# NukeNanny.net
KiCad netlist of a schematic drawn in EAGLE
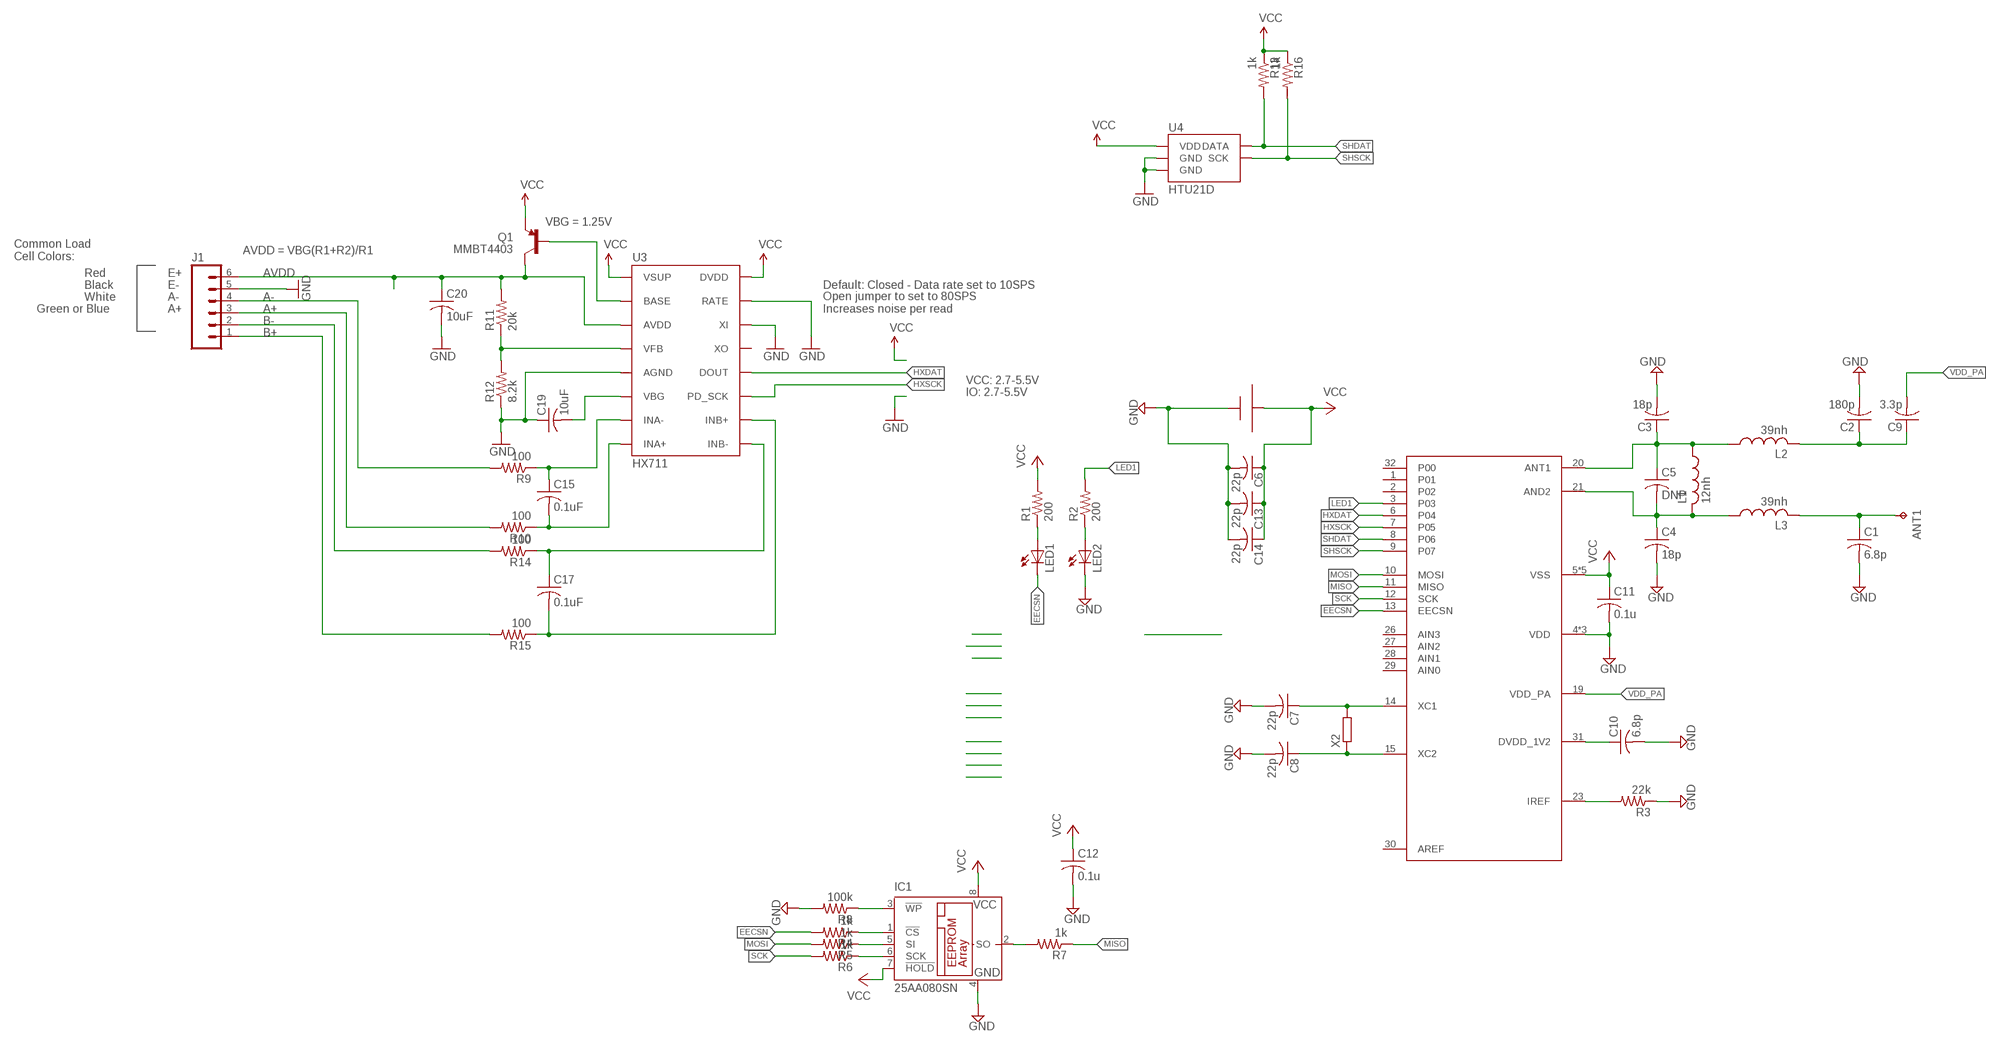
[diagram p0: schematic, sheet 1]

(export (version "E")
  (design (tool "Eeschema 10.0.6"))
  (components
    (comp (ref "ANT1")
      (value "TPB2,54")
      (footprint "eagle-import:B2,54")
      (libsource (lib "eagle-import") (part "TPB2,54"))
    )
    (comp (ref "C1")
      (value "6.8p")
      (footprint "eagle-import:C0805")
      (libsource (lib "eagle-import") (part "C-USC0805"))
    )
    (comp (ref "C2")
      (value "180p")
      (footprint "eagle-import:C0805")
      (libsource (lib "eagle-import") (part "C-USC0805"))
    )
    (comp (ref "C3")
      (value "18p")
      (footprint "eagle-import:C0805")
      (libsource (lib "eagle-import") (part "C-USC0805"))
    )
    (comp (ref "C4")
      (value "18p")
      (footprint "eagle-import:C0805")
      (libsource (lib "eagle-import") (part "C-USC0805"))
    )
    (comp (ref "C5")
      (value "DNP")
      (footprint "eagle-import:C0805")
      (libsource (lib "eagle-import") (part "C-USC0805"))
    )
    (comp (ref "C6")
      (value "22p")
      (footprint "eagle-import:C1206")
      (libsource (lib "eagle-import") (part "C-USC1206"))
    )
    (comp (ref "C7")
      (value "22p")
      (footprint "eagle-import:C0805")
      (libsource (lib "eagle-import") (part "C-USC0805"))
    )
    (comp (ref "C8")
      (value "22p")
      (footprint "eagle-import:C0805")
      (libsource (lib "eagle-import") (part "C-USC0805"))
    )
    (comp (ref "C9")
      (value "3.3p")
      (footprint "eagle-import:C0805")
      (libsource (lib "eagle-import") (part "C-USC0805"))
    )
    (comp (ref "C10")
      (value "6.8p")
      (footprint "eagle-import:C0805")
      (libsource (lib "eagle-import") (part "C-USC0805"))
    )
    (comp (ref "C11")
      (value "0.1u")
      (footprint "eagle-import:C0805")
      (libsource (lib "eagle-import") (part "C-USC0805"))
    )
    (comp (ref "C12")
      (value "0.1u")
      (footprint "eagle-import:C0805")
      (libsource (lib "eagle-import") (part "C-USC0805"))
    )
    (comp (ref "C13")
      (value "22p")
      (footprint "eagle-import:C1206")
      (libsource (lib "eagle-import") (part "C-USC1206"))
    )
    (comp (ref "C14")
      (value "22p")
      (footprint "eagle-import:C1206")
      (libsource (lib "eagle-import") (part "C-USC1206"))
    )
    (comp (ref "C15")
      (value "0.1uF")
      (footprint "eagle-import:C0805")
      (libsource (lib "eagle-import") (part "C-USC0805"))
    )
    (comp (ref "C17")
      (value "0.1uF")
      (footprint "eagle-import:C0805")
      (libsource (lib "eagle-import") (part "C-USC0805"))
    )
    (comp (ref "C19")
      (value "10uF")
      (footprint "eagle-import:C0805")
      (libsource (lib "eagle-import") (part "C-USC0805"))
    )
    (comp (ref "C20")
      (value "10uF")
      (footprint "eagle-import:C0805")
      (libsource (lib "eagle-import") (part "C-USC0805"))
    )
    (comp (ref "IC1")
      (value "25AA080SN")
      (footprint "eagle-import:SO-08")
      (fields (field (name "MF") "MICROCHIP") (field (name "MPN") "25AA080/SN"))
      (libsource (lib "eagle-import") (part "25SNAA080"))
    )
    (comp (ref "J1")
      (value "M06SMD-1MM")
      (footprint "eagle-import:1X06-1MM")
      (libsource (lib "eagle-import") (part "M06SMD-1MM"))
    )
    (comp (ref "L1")
      (value "12nh")
      (footprint "eagle-import:L2012C")
      (libsource (lib "eagle-import") (part "L-USL2012C"))
    )
    (comp (ref "L2")
      (value "39nh")
      (footprint "eagle-import:L2012C")
      (libsource (lib "eagle-import") (part "L-USL2012C"))
    )
    (comp (ref "L3")
      (value "39nh")
      (footprint "eagle-import:L2012C")
      (libsource (lib "eagle-import") (part "L-USL2012C"))
    )
    (comp (ref "LED1")
      (value "LEDCHIP-LED0805")
      (footprint "eagle-import:CHIP-LED0805")
      (libsource (lib "eagle-import") (part "LEDCHIP-LED0805"))
    )
    (comp (ref "LED2")
      (value "LEDCHIP-LED0805")
      (footprint "eagle-import:CHIP-LED0805")
      (libsource (lib "eagle-import") (part "LEDCHIP-LED0805"))
    )
    (comp (ref "Q1")
      (value "MMBT4403")
      (footprint "eagle-import:SOT23-3")
      (libsource (lib "eagle-import") (part "TRANSISTOR_PNPMMBT4403"))
    )
    (comp (ref "R1")
      (value "200")
      (footprint "eagle-import:R0805")
      (libsource (lib "eagle-import") (part "R-US_R0805"))
    )
    (comp (ref "R2")
      (value "200")
      (footprint "eagle-import:R0805")
      (libsource (lib "eagle-import") (part "R-US_R0805"))
    )
    (comp (ref "R3")
      (value "22k")
      (footprint "eagle-import:R0805")
      (libsource (lib "eagle-import") (part "R-US_R0805"))
    )
    (comp (ref "R4")
      (value "1k")
      (footprint "eagle-import:R0805")
      (libsource (lib "eagle-import") (part "R-US_R0805"))
    )
    (comp (ref "R5")
      (value "1k")
      (footprint "eagle-import:R0805")
      (libsource (lib "eagle-import") (part "R-US_R0805"))
    )
    (comp (ref "R6")
      (value "1k")
      (footprint "eagle-import:R0805")
      (libsource (lib "eagle-import") (part "R-US_R0805"))
    )
    (comp (ref "R7")
      (value "1k")
      (footprint "eagle-import:R0805")
      (libsource (lib "eagle-import") (part "R-US_R0805"))
    )
    (comp (ref "R8")
      (value "100k")
      (footprint "eagle-import:R0805")
      (libsource (lib "eagle-import") (part "R-US_R0805"))
    )
    (comp (ref "R9")
      (value "100")
      (footprint "eagle-import:R0805")
      (libsource (lib "eagle-import") (part "R-US_R0805"))
    )
    (comp (ref "R10")
      (value "100")
      (footprint "eagle-import:R0805")
      (libsource (lib "eagle-import") (part "R-US_R0805"))
    )
    (comp (ref "R11")
      (value "20k")
      (footprint "eagle-import:R0805")
      (libsource (lib "eagle-import") (part "R-US_R0805"))
    )
    (comp (ref "R12")
      (value "8.2k")
      (footprint "eagle-import:R0805")
      (libsource (lib "eagle-import") (part "R-US_R0805"))
    )
    (comp (ref "R13")
      (value "1k")
      (footprint "eagle-import:R0805")
      (libsource (lib "eagle-import") (part "R-US_R0805"))
    )
    (comp (ref "R14")
      (value "100")
      (footprint "eagle-import:R0805")
      (libsource (lib "eagle-import") (part "R-US_R0805"))
    )
    (comp (ref "R15")
      (value "100")
      (footprint "eagle-import:R0805")
      (libsource (lib "eagle-import") (part "R-US_R0805"))
    )
    (comp (ref "R16")
      (value "1k")
      (footprint "eagle-import:R0805")
      (libsource (lib "eagle-import") (part "R-US_R0805"))
    )
    (comp (ref "U$1")
      (value "NRF9E5")
      (footprint "eagle-import:32QFN-THIN")
      (libsource (lib "eagle-import") (part "NRF9E5"))
    )
    (comp (ref "U1")
      (value "CR2032")
      (footprint "eagle-import:SMT_CR2032_HOLDER")
      (libsource (lib "eagle-import") (part "CR2032"))
    )
    (comp (ref "U3")
      (value "HX711")
      (footprint "eagle-import:SO16")
      (libsource (lib "eagle-import") (part "HX711HX711"))
    )
    (comp (ref "U4")
      (value "HTU21D")
      (footprint "eagle-import:HTU21D")
      (libsource (lib "eagle-import") (part "HTU21DSMD"))
    )
    (comp (ref "X2")
      (value "R-EU_R3225")
      (footprint "eagle-import:R3225")
      (libsource (lib "eagle-import") (part "R-EU_R3225"))
    )
  )
  (nets
    (net (code "1") (name "/A+") (class "Default")
      (node (ref "J1") (pin "3") (pinfunction "3_3") (pintype "passive"))
      (node (ref "R10") (pin "2") (pinfunction "2_2") (pintype "passive"))
    )
    (net (code "2") (name "/A-") (class "Default")
      (node (ref "J1") (pin "4") (pinfunction "4_4") (pintype "passive"))
      (node (ref "R9") (pin "2") (pinfunction "2_2") (pintype "passive"))
    )
    (net (code "3") (name "/AVDD") (class "Default")
      (node (ref "C20") (pin "1") (pinfunction "1_1") (pintype "passive"))
      (node (ref "J1") (pin "6") (pinfunction "6_6") (pintype "passive"))
      (node (ref "Q1") (pin "3") (pinfunction "C_3") (pintype "passive"))
      (node (ref "R11") (pin "2") (pinfunction "2_2") (pintype "passive"))
      (node (ref "U3") (pin "3") (pinfunction "AVDD_3") (pintype "bidirectional"))
    )
    (net (code "4") (name "/B+") (class "Default")
      (node (ref "J1") (pin "1") (pinfunction "1_1") (pintype "passive"))
      (node (ref "R15") (pin "2") (pinfunction "2_2") (pintype "passive"))
    )
    (net (code "5") (name "/B-") (class "Default")
      (node (ref "J1") (pin "2") (pinfunction "2_2") (pintype "passive"))
      (node (ref "R14") (pin "2") (pinfunction "2_2") (pintype "passive"))
    )
    (net (code "6") (name "EECSN") (class "Default")
      (node (ref "LED1") (pin "C") (pinfunction "C_C") (pintype "passive"))
      (node (ref "R4") (pin "2") (pinfunction "2_2") (pintype "passive"))
      (node (ref "U$1") (pin "13") (pinfunction "EECSN_13") (pintype "bidirectional"))
    )
    (net (code "7") (name "GND") (class "Default")
      (node (ref "C1") (pin "2") (pinfunction "2_2") (pintype "passive"))
      (node (ref "C10") (pin "2") (pinfunction "2_2") (pintype "passive"))
      (node (ref "C11") (pin "2") (pinfunction "2_2") (pintype "passive"))
      (node (ref "C12") (pin "2") (pinfunction "2_2") (pintype "passive"))
      (node (ref "C13") (pin "2") (pinfunction "2_2") (pintype "passive"))
      (node (ref "C14") (pin "2") (pinfunction "2_2") (pintype "passive"))
      (node (ref "C19") (pin "1") (pinfunction "1_1") (pintype "passive"))
      (node (ref "C2") (pin "2") (pinfunction "2_2") (pintype "passive"))
      (node (ref "C20") (pin "2") (pinfunction "2_2") (pintype "passive"))
      (node (ref "C3") (pin "2") (pinfunction "2_2") (pintype "passive"))
      (node (ref "C4") (pin "2") (pinfunction "2_2") (pintype "passive"))
      (node (ref "C6") (pin "2") (pinfunction "2_2") (pintype "passive"))
      (node (ref "C7") (pin "2") (pinfunction "2_2") (pintype "passive"))
      (node (ref "C8") (pin "2") (pinfunction "2_2") (pintype "passive"))
      (node (ref "IC1") (pin "4") (pinfunction "GND_4") (pintype "power_in"))
      (node (ref "J1") (pin "5") (pinfunction "5_5") (pintype "passive"))
      (node (ref "LED2") (pin "C") (pinfunction "C_C") (pintype "passive"))
      (node (ref "R12") (pin "1") (pinfunction "1_1") (pintype "passive"))
      (node (ref "R3") (pin "1") (pinfunction "1_1") (pintype "passive"))
      (node (ref "R8") (pin "2") (pinfunction "2_2") (pintype "passive"))
      (node (ref "U$1") (pin "17") (pinfunction "VDD_17") (pintype "bidirectional"))
      (node (ref "U$1") (pin "25") (pinfunction "VDD_25") (pintype "bidirectional"))
      (node (ref "U$1") (pin "4") (pinfunction "VDD_4") (pintype "bidirectional"))
      (node (ref "U1") (pin "-") (pinfunction "-_-") (pintype "bidirectional"))
      (node (ref "U3") (pin "14") (pinfunction "XI_14") (pintype "bidirectional"))
      (node (ref "U3") (pin "15") (pinfunction "RATE_15") (pintype "bidirectional"))
      (node (ref "U3") (pin "5") (pinfunction "AGND_5") (pintype "bidirectional"))
      (node (ref "U4") (pin "7") (pinfunction "GND_7") (pintype "power_in"))
      (node (ref "U4") (pin "GND") (pinfunction "GND_GND") (pintype "power_in"))
    )
    (net (code "8") (name "HXDAT") (class "Default")
      (node (ref "U$1") (pin "6") (pinfunction "P04_6") (pintype "bidirectional"))
      (node (ref "U3") (pin "12") (pinfunction "DOUT_12") (pintype "bidirectional"))
    )
    (net (code "9") (name "HXSCK") (class "Default")
      (node (ref "U$1") (pin "7") (pinfunction "P05_7") (pintype "bidirectional"))
      (node (ref "U3") (pin "11") (pinfunction "PD_SCK_11") (pintype "bidirectional"))
    )
    (net (code "10") (name "LED1") (class "Default")
      (node (ref "R2") (pin "2") (pinfunction "2_2") (pintype "passive"))
      (node (ref "U$1") (pin "3") (pinfunction "P03_3") (pintype "bidirectional"))
    )
    (net (code "11") (name "MISO") (class "Default")
      (node (ref "R7") (pin "1") (pinfunction "1_1") (pintype "passive"))
      (node (ref "U$1") (pin "11") (pinfunction "MISO_11") (pintype "bidirectional"))
    )
    (net (code "12") (name "MOSI") (class "Default")
      (node (ref "R5") (pin "2") (pinfunction "2_2") (pintype "passive"))
      (node (ref "U$1") (pin "10") (pinfunction "MOSI_10") (pintype "bidirectional"))
    )
    (net (code "13") (name "Net-(ANT1-PadTP)") (class "Default")
      (node (ref "ANT1") (pin "TP") (pinfunction "TP_TP") (pintype "input"))
      (node (ref "C1") (pin "1") (pinfunction "1_1") (pintype "passive"))
      (node (ref "L3") (pin "2") (pinfunction "2_2") (pintype "passive"))
    )
    (net (code "14") (name "Net-(C2-Pad1)") (class "Default")
      (node (ref "C2") (pin "1") (pinfunction "1_1") (pintype "passive"))
      (node (ref "C9") (pin "1") (pinfunction "1_1") (pintype "passive"))
      (node (ref "L2") (pin "2") (pinfunction "2_2") (pintype "passive"))
    )
    (net (code "15") (name "Net-(IC1-SCK)") (class "Default")
      (node (ref "IC1") (pin "6") (pinfunction "SCK_6") (pintype "input"))
      (node (ref "R6") (pin "1") (pinfunction "1_1") (pintype "passive"))
    )
    (net (code "16") (name "Net-(IC1-SI)") (class "Default")
      (node (ref "IC1") (pin "5") (pinfunction "SI_5") (pintype "input"))
      (node (ref "R5") (pin "1") (pinfunction "1_1") (pintype "passive"))
    )
    (net (code "17") (name "Net-(IC1-SO)") (class "Default")
      (node (ref "IC1") (pin "2") (pinfunction "SO_2") (pintype "bidirectional"))
      (node (ref "R7") (pin "2") (pinfunction "2_2") (pintype "passive"))
    )
    (net (code "18") (name "Net-(IC1-~{CS})") (class "Default")
      (node (ref "IC1") (pin "1") (pinfunction "~{CS}_1") (pintype "input"))
      (node (ref "R4") (pin "1") (pinfunction "1_1") (pintype "passive"))
    )
    (net (code "19") (name "Net-(IC1-~{WP})") (class "Default")
      (node (ref "IC1") (pin "3") (pinfunction "~{WP}_3") (pintype "input"))
      (node (ref "R8") (pin "1") (pinfunction "1_1") (pintype "passive"))
    )
    (net (code "20") (name "Net-(LED1-PadA)") (class "Default")
      (node (ref "LED1") (pin "A") (pinfunction "A_A") (pintype "passive"))
      (node (ref "R1") (pin "1") (pinfunction "1_1") (pintype "passive"))
    )
    (net (code "21") (name "Net-(LED2-PadA)") (class "Default")
      (node (ref "LED2") (pin "A") (pinfunction "A_A") (pintype "passive"))
      (node (ref "R2") (pin "1") (pinfunction "1_1") (pintype "passive"))
    )
    (net (code "22") (name "Net-(Q1-B)") (class "Default")
      (node (ref "Q1") (pin "1") (pinfunction "B_1") (pintype "passive"))
      (node (ref "U3") (pin "2") (pinfunction "BASE_2") (pintype "bidirectional"))
    )
    (net (code "23") (name "Net-(U$1-AND2)") (class "Default")
      (node (ref "C4") (pin "1") (pinfunction "1_1") (pintype "passive"))
      (node (ref "C5") (pin "2") (pinfunction "2_2") (pintype "passive"))
      (node (ref "L1") (pin "2") (pinfunction "2_2") (pintype "passive"))
      (node (ref "L3") (pin "1") (pinfunction "1_1") (pintype "passive"))
      (node (ref "U$1") (pin "21") (pinfunction "AND2_21") (pintype "bidirectional"))
    )
    (net (code "24") (name "Net-(U$1-ANT1)") (class "Default")
      (node (ref "C3") (pin "1") (pinfunction "1_1") (pintype "passive"))
      (node (ref "C5") (pin "1") (pinfunction "1_1") (pintype "passive"))
      (node (ref "L1") (pin "1") (pinfunction "1_1") (pintype "passive"))
      (node (ref "L2") (pin "1") (pinfunction "1_1") (pintype "passive"))
      (node (ref "U$1") (pin "20") (pinfunction "ANT1_20") (pintype "bidirectional"))
    )
    (net (code "25") (name "Net-(U$1-DVDD_1V2)") (class "Default")
      (node (ref "C10") (pin "1") (pinfunction "1_1") (pintype "passive"))
      (node (ref "U$1") (pin "31") (pinfunction "DVDD_1V2_31") (pintype "bidirectional"))
    )
    (net (code "26") (name "Net-(U$1-IREF)") (class "Default")
      (node (ref "R3") (pin "2") (pinfunction "2_2") (pintype "passive"))
      (node (ref "U$1") (pin "23") (pinfunction "IREF_23") (pintype "bidirectional"))
    )
    (net (code "27") (name "Net-(U$1-XC1)") (class "Default")
      (node (ref "C7") (pin "1") (pinfunction "1_1") (pintype "passive"))
      (node (ref "U$1") (pin "14") (pinfunction "XC1_14") (pintype "bidirectional"))
      (node (ref "X2") (pin "2") (pinfunction "2_2") (pintype "passive"))
    )
    (net (code "28") (name "Net-(U$1-XC2)") (class "Default")
      (node (ref "C8") (pin "1") (pinfunction "1_1") (pintype "passive"))
      (node (ref "U$1") (pin "15") (pinfunction "XC2_15") (pintype "bidirectional"))
      (node (ref "X2") (pin "1") (pinfunction "1_1") (pintype "passive"))
    )
    (net (code "29") (name "Net-(U3-INA+)") (class "Default")
      (node (ref "C15") (pin "2") (pinfunction "2_2") (pintype "passive"))
      (node (ref "R10") (pin "1") (pinfunction "1_1") (pintype "passive"))
      (node (ref "U3") (pin "8") (pinfunction "INA+_8") (pintype "bidirectional"))
    )
    (net (code "30") (name "Net-(U3-INA-)") (class "Default")
      (node (ref "C15") (pin "1") (pinfunction "1_1") (pintype "passive"))
      (node (ref "R9") (pin "1") (pinfunction "1_1") (pintype "passive"))
      (node (ref "U3") (pin "7") (pinfunction "INA-_7") (pintype "bidirectional"))
    )
    (net (code "31") (name "Net-(U3-INB+)") (class "Default")
      (node (ref "C17") (pin "2") (pinfunction "2_2") (pintype "passive"))
      (node (ref "R15") (pin "1") (pinfunction "1_1") (pintype "passive"))
      (node (ref "U3") (pin "10") (pinfunction "INB+_10") (pintype "bidirectional"))
    )
    (net (code "32") (name "Net-(U3-INB-)") (class "Default")
      (node (ref "C17") (pin "1") (pinfunction "1_1") (pintype "passive"))
      (node (ref "R14") (pin "1") (pinfunction "1_1") (pintype "passive"))
      (node (ref "U3") (pin "9") (pinfunction "INB-_9") (pintype "bidirectional"))
    )
    (net (code "33") (name "Net-(U3-VBG)") (class "Default")
      (node (ref "C19") (pin "2") (pinfunction "2_2") (pintype "passive"))
      (node (ref "U3") (pin "6") (pinfunction "VBG_6") (pintype "bidirectional"))
    )
    (net (code "34") (name "Net-(U3-VFB)") (class "Default")
      (node (ref "R11") (pin "1") (pinfunction "1_1") (pintype "passive"))
      (node (ref "R12") (pin "2") (pinfunction "2_2") (pintype "passive"))
      (node (ref "U3") (pin "4") (pinfunction "VFB_4") (pintype "bidirectional"))
    )
    (net (code "35") (name "SCK") (class "Default")
      (node (ref "R6") (pin "2") (pinfunction "2_2") (pintype "passive"))
      (node (ref "U$1") (pin "12") (pinfunction "SCK_12") (pintype "bidirectional"))
    )
    (net (code "36") (name "SHDAT") (class "Default")
      (node (ref "R13") (pin "2") (pinfunction "2_2") (pintype "passive"))
      (node (ref "U$1") (pin "8") (pinfunction "P06_8") (pintype "bidirectional"))
      (node (ref "U4") (pin "DATA") (pinfunction "DATA_DATA") (pintype "bidirectional"))
    )
    (net (code "37") (name "SHSCK") (class "Default")
      (node (ref "R16") (pin "2") (pinfunction "2_2") (pintype "passive"))
      (node (ref "U$1") (pin "9") (pinfunction "P07_9") (pintype "bidirectional"))
      (node (ref "U4") (pin "SCK") (pinfunction "SCK_SCK") (pintype "input"))
    )
    (net (code "38") (name "VCC") (class "Default")
      (node (ref "C11") (pin "1") (pinfunction "1_1") (pintype "passive"))
      (node (ref "C12") (pin "1") (pinfunction "1_1") (pintype "passive"))
      (node (ref "C13") (pin "1") (pinfunction "1_1") (pintype "passive"))
      (node (ref "C14") (pin "1") (pinfunction "1_1") (pintype "passive"))
      (node (ref "C6") (pin "1") (pinfunction "1_1") (pintype "passive"))
      (node (ref "IC1") (pin "7") (pinfunction "~{HOLD}_7") (pintype "input"))
      (node (ref "IC1") (pin "8") (pinfunction "VCC_8") (pintype "power_in"))
      (node (ref "Q1") (pin "2") (pinfunction "E_2") (pintype "passive"))
      (node (ref "R1") (pin "2") (pinfunction "2_2") (pintype "passive"))
      (node (ref "R13") (pin "1") (pinfunction "1_1") (pintype "passive"))
      (node (ref "R16") (pin "1") (pinfunction "1_1") (pintype "passive"))
      (node (ref "U$1") (pin "16") (pinfunction "VSS_16") (pintype "bidirectional"))
      (node (ref "U$1") (pin "18") (pinfunction "VSS_18") (pintype "bidirectional"))
      (node (ref "U$1") (pin "22") (pinfunction "VSS_22") (pintype "bidirectional"))
      (node (ref "U$1") (pin "24") (pinfunction "VSS_24") (pintype "bidirectional"))
      (node (ref "U$1") (pin "5") (pinfunction "VSS_5") (pintype "bidirectional"))
      (node (ref "U1") (pin "+") (pinfunction "+_+") (pintype "bidirectional"))
      (node (ref "U3") (pin "1") (pinfunction "VSUP_1") (pintype "bidirectional"))
      (node (ref "U3") (pin "16") (pinfunction "DVDD_16") (pintype "bidirectional"))
      (node (ref "U4") (pin "VDD") (pinfunction "VDD_VDD") (pintype "power_in"))
    )
    (net (code "39") (name "VDD_PA") (class "Default")
      (node (ref "C9") (pin "2") (pinfunction "2_2") (pintype "passive"))
      (node (ref "U$1") (pin "19") (pinfunction "VDD_PA_19") (pintype "bidirectional"))
    )
    (net (code "40") (name "unconnected-(U$1-AIN0-Pad29)") (class "Default")
      (node (ref "U$1") (pin "29") (pinfunction "AIN0_29") (pintype "bidirectional"))
    )
    (net (code "41") (name "unconnected-(U$1-AIN1-Pad28)") (class "Default")
      (node (ref "U$1") (pin "28") (pinfunction "AIN1_28") (pintype "bidirectional"))
    )
    (net (code "42") (name "unconnected-(U$1-AIN2-Pad27)") (class "Default")
      (node (ref "U$1") (pin "27") (pinfunction "AIN2_27") (pintype "bidirectional"))
    )
    (net (code "43") (name "unconnected-(U$1-AIN3-Pad26)") (class "Default")
      (node (ref "U$1") (pin "26") (pinfunction "AIN3_26") (pintype "bidirectional"))
    )
    (net (code "44") (name "unconnected-(U$1-AREF-Pad30)") (class "Default")
      (node (ref "U$1") (pin "30") (pinfunction "AREF_30") (pintype "bidirectional"))
    )
    (net (code "45") (name "unconnected-(U$1-P00-Pad32)") (class "Default")
      (node (ref "U$1") (pin "32") (pinfunction "P00_32") (pintype "bidirectional"))
    )
    (net (code "46") (name "unconnected-(U$1-P01-Pad1)") (class "Default")
      (node (ref "U$1") (pin "1") (pinfunction "P01_1") (pintype "bidirectional"))
    )
    (net (code "47") (name "unconnected-(U$1-P02-Pad2)") (class "Default")
      (node (ref "U$1") (pin "2") (pinfunction "P02_2") (pintype "bidirectional"))
    )
    (net (code "48") (name "unconnected-(U3-XO-Pad13)") (class "Default")
      (node (ref "U3") (pin "13") (pinfunction "XO_13") (pintype "bidirectional"))
    )
  )
)
